# PiezoPreamp_V3.net
KiCad netlist of a schematic drawn in EAGLE
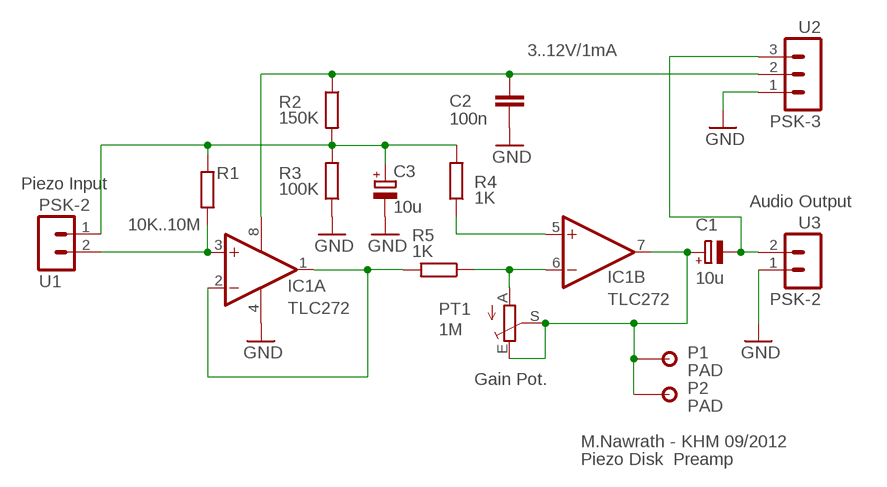
[diagram p0: schematic, sheet 1]

(export (version "E")
  (design (tool "Eeschema 10.0.6"))
  (components
    (comp (ref "C1")
      (value "10u")
      (footprint "eagle-import:E2,5-5")
      (libsource (lib "eagle-import") (part "CPOL-EUE2.5-5"))
    )
    (comp (ref "C2")
      (value "100n")
      (footprint "eagle-import:C025-025X050")
      (libsource (lib "eagle-import") (part "C-EU025-025X050"))
    )
    (comp (ref "C3")
      (value "10u")
      (footprint "eagle-import:E2,5-5")
      (libsource (lib "eagle-import") (part "CPOL-EUE2.5-5"))
    )
    (comp (ref "IC1")
      (value "TLC272")
      (footprint "eagle-import:DIL08")
      (libsource (lib "eagle-import") (part "TLC272P"))
    )
    (comp (ref "P1")
      (value "PAD")
      (footprint "eagle-import:PAD127L1")
      (libsource (lib "eagle-import") (part "PADL2"))
    )
    (comp (ref "P2")
      (value "PAD")
      (footprint "eagle-import:PAD127L1")
      (libsource (lib "eagle-import") (part "PADL2"))
    )
    (comp (ref "PT1")
      (value "1M")
      (footprint "eagle-import:CA6V")
      (libsource (lib "eagle-import") (part "TRIM_EU-CA6V"))
    )
    (comp (ref "R1")
      (value "10K..10M")
      (footprint "eagle-import:0204_5")
      (libsource (lib "eagle-import") (part "R-EU_0204/5"))
    )
    (comp (ref "R2")
      (value "150K")
      (footprint "eagle-import:0204_5")
      (libsource (lib "eagle-import") (part "R-EU_0204/5"))
    )
    (comp (ref "R3")
      (value "100K")
      (footprint "eagle-import:0204_5")
      (libsource (lib "eagle-import") (part "R-EU_0204/5"))
    )
    (comp (ref "R4")
      (value "1K")
      (footprint "eagle-import:0204_5")
      (libsource (lib "eagle-import") (part "R-EU_0204/5"))
    )
    (comp (ref "R5")
      (value "1K")
      (footprint "eagle-import:0204_5")
      (libsource (lib "eagle-import") (part "R-EU_0204/5"))
    )
    (comp (ref "U1")
      (value "PSK-2")
      (footprint "eagle-import:PSK254_2")
      (libsource (lib "eagle-import") (part "PSK-2"))
    )
    (comp (ref "U2")
      (value "PSK-3")
      (footprint "eagle-import:PSK254_3")
      (libsource (lib "eagle-import") (part "PSK-3"))
    )
    (comp (ref "U3")
      (value "PSK-2")
      (footprint "eagle-import:PSK254_2")
      (libsource (lib "eagle-import") (part "PSK-2"))
    )
  )
  (nets
    (net (code "1") (name "GND") (class "Default")
      (node (ref "C2") (pin "1") (pinfunction "1_1") (pintype "passive"))
      (node (ref "C3") (pin "-") (pinfunction "-_-") (pintype "passive"))
      (node (ref "IC1") (pin "4") (pinfunction "V-_4") (pintype "power_in"))
      (node (ref "R3") (pin "1") (pinfunction "1_1") (pintype "passive"))
      (node (ref "U2") (pin "1") (pinfunction "1_1") (pintype "passive"))
      (node (ref "U3") (pin "1") (pinfunction "1_1") (pintype "passive"))
    )
    (net (code "2") (name "Net-(C1-Pad-)") (class "Default")
      (node (ref "C1") (pin "-") (pinfunction "-_-") (pintype "passive"))
      (node (ref "U2") (pin "3") (pinfunction "3_3") (pintype "passive"))
      (node (ref "U3") (pin "2") (pinfunction "2_2") (pintype "passive"))
    )
    (net (code "3") (name "Net-(C3-Pad+)") (class "Default")
      (node (ref "C3") (pin "+") (pinfunction "+_+") (pintype "passive"))
      (node (ref "R1") (pin "2") (pinfunction "2_2") (pintype "passive"))
      (node (ref "R2") (pin "2") (pinfunction "2_2") (pintype "passive"))
      (node (ref "R3") (pin "2") (pinfunction "2_2") (pintype "passive"))
      (node (ref "R4") (pin "2") (pinfunction "2_2") (pintype "passive"))
      (node (ref "U1") (pin "1") (pinfunction "1_1") (pintype "passive"))
    )
    (net (code "4") (name "Net-(IC1A-+IN)") (class "Default")
      (node (ref "IC1") (pin "3") (pinfunction "+IN_3") (pintype "input"))
      (node (ref "R1") (pin "1") (pinfunction "1_1") (pintype "passive"))
      (node (ref "U1") (pin "2") (pinfunction "2_2") (pintype "passive"))
    )
    (net (code "5") (name "Net-(IC1A--IN)") (class "Default")
      (node (ref "IC1") (pin "1") (pinfunction "OUT_1") (pintype "output"))
      (node (ref "IC1") (pin "2") (pinfunction "-IN_2") (pintype "input"))
      (node (ref "R5") (pin "2") (pinfunction "2_2") (pintype "passive"))
    )
    (net (code "6") (name "Net-(IC1B-+IN)") (class "Default")
      (node (ref "IC1") (pin "5") (pinfunction "+IN_5") (pintype "input"))
      (node (ref "R4") (pin "1") (pinfunction "1_1") (pintype "passive"))
    )
    (net (code "7") (name "Net-(IC1B--IN)") (class "Default")
      (node (ref "IC1") (pin "6") (pinfunction "-IN_6") (pintype "input"))
      (node (ref "PT1") (pin "A") (pinfunction "A_A") (pintype "passive"))
      (node (ref "R5") (pin "1") (pinfunction "1_1") (pintype "passive"))
    )
    (net (code "8") (name "Net-(IC1B-OUT)") (class "Default")
      (node (ref "C1") (pin "+") (pinfunction "+_+") (pintype "passive"))
      (node (ref "IC1") (pin "7") (pinfunction "OUT_7") (pintype "output"))
      (node (ref "P1") (pin "P$2") (pinfunction "1_P$2") (pintype "passive"))
      (node (ref "P2") (pin "P$2") (pinfunction "1_P$2") (pintype "passive"))
      (node (ref "PT1") (pin "E") (pinfunction "E_E") (pintype "passive"))
      (node (ref "PT1") (pin "S") (pinfunction "S_S") (pintype "passive"))
    )
    (net (code "9") (name "Net-(IC1C-V+)") (class "Default")
      (node (ref "C2") (pin "2") (pinfunction "2_2") (pintype "passive"))
      (node (ref "IC1") (pin "8") (pinfunction "V+_8") (pintype "power_in"))
      (node (ref "R2") (pin "1") (pinfunction "1_1") (pintype "passive"))
      (node (ref "U2") (pin "2") (pinfunction "2_2") (pintype "passive"))
    )
  )
)
